# ATTiny85_Breadboard.net
KiCad netlist of a schematic drawn in EAGLE
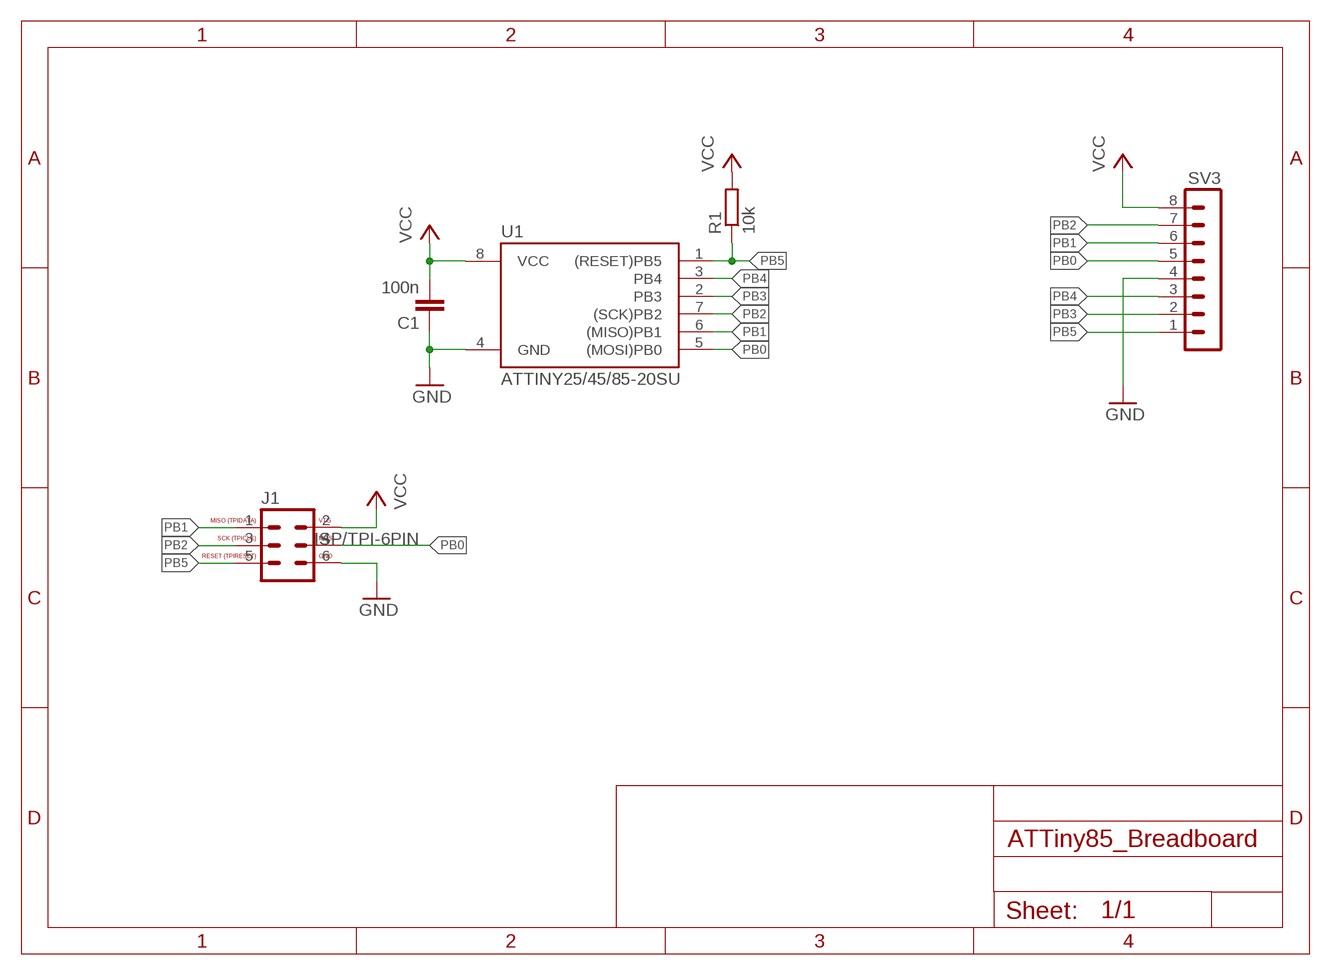
[diagram p0: schematic, sheet 1]

(export (version "E")
  (design (tool "Eeschema 10.0.6"))
  (components
    (comp (ref "C1")
      (value "100n")
      (footprint "eagle-import:C0402")
      (libsource (lib "eagle-import") (part "C-EUC0402"))
    )
    (comp (ref "J1")
      (value "ISP/TPI-6PIN")
      (footprint "eagle-import:ML6")
      (libsource (lib "eagle-import") (part "ISP/TPI-6PIN"))
    )
    (comp (ref "R1")
      (value "10k")
      (footprint "eagle-import:R0402")
      (libsource (lib "eagle-import") (part "R-EU_R0402"))
    )
    (comp (ref "SV3")
      (value "MA08-1")
      (footprint "eagle-import:MA08-1")
      (libsource (lib "eagle-import") (part "MA08-1"))
    )
    (comp (ref "U1")
      (value "ATTINY25/45/85-20SU")
      (footprint "eagle-import:SOIC8_200")
      (libsource (lib "eagle-import") (part "ATTINY25/45/85-20SU"))
    )
  )
  (nets
    (net (code "1") (name "GND") (class "Default")
      (node (ref "C1") (pin "1") (pinfunction "1_1") (pintype "passive"))
      (node (ref "J1") (pin "6") (pinfunction "6_6") (pintype "passive"))
      (node (ref "SV3") (pin "4") (pinfunction "4_4") (pintype "passive"))
      (node (ref "U1") (pin "4") (pinfunction "GND_4") (pintype "power_in"))
    )
    (net (code "2") (name "PB0") (class "Default")
      (node (ref "J1") (pin "4") (pinfunction "4_4") (pintype "passive"))
      (node (ref "SV3") (pin "5") (pinfunction "5_5") (pintype "passive"))
      (node (ref "U1") (pin "5") (pinfunction "(MOSI)PB0_5") (pintype "bidirectional"))
    )
    (net (code "3") (name "PB1") (class "Default")
      (node (ref "J1") (pin "1") (pinfunction "1_1") (pintype "passive"))
      (node (ref "SV3") (pin "6") (pinfunction "6_6") (pintype "passive"))
      (node (ref "U1") (pin "6") (pinfunction "(MISO)PB1_6") (pintype "bidirectional"))
    )
    (net (code "4") (name "PB2") (class "Default")
      (node (ref "J1") (pin "3") (pinfunction "3_3") (pintype "passive"))
      (node (ref "SV3") (pin "7") (pinfunction "7_7") (pintype "passive"))
      (node (ref "U1") (pin "7") (pinfunction "(SCK)PB2_7") (pintype "bidirectional"))
    )
    (net (code "5") (name "PB3") (class "Default")
      (node (ref "SV3") (pin "2") (pinfunction "2_2") (pintype "passive"))
      (node (ref "U1") (pin "2") (pinfunction "PB3_2") (pintype "bidirectional"))
    )
    (net (code "6") (name "PB4") (class "Default")
      (node (ref "SV3") (pin "3") (pinfunction "3_3") (pintype "passive"))
      (node (ref "U1") (pin "3") (pinfunction "PB4_3") (pintype "bidirectional"))
    )
    (net (code "7") (name "PB5") (class "Default")
      (node (ref "J1") (pin "5") (pinfunction "5_5") (pintype "passive"))
      (node (ref "R1") (pin "1") (pinfunction "1_1") (pintype "passive"))
      (node (ref "SV3") (pin "1") (pinfunction "1_1") (pintype "passive"))
      (node (ref "U1") (pin "1") (pinfunction "(RESET)PB5_1") (pintype "bidirectional"))
    )
    (net (code "8") (name "VCC") (class "Default")
      (node (ref "C1") (pin "2") (pinfunction "2_2") (pintype "passive"))
      (node (ref "J1") (pin "2") (pinfunction "2_2") (pintype "passive"))
      (node (ref "R1") (pin "2") (pinfunction "2_2") (pintype "passive"))
      (node (ref "SV3") (pin "8") (pinfunction "8_8") (pintype "passive"))
      (node (ref "U1") (pin "8") (pinfunction "VCC_8") (pintype "power_in"))
    )
  )
)
